# TSC-schema.net
KiCad netlist of a schematic drawn in EAGLE
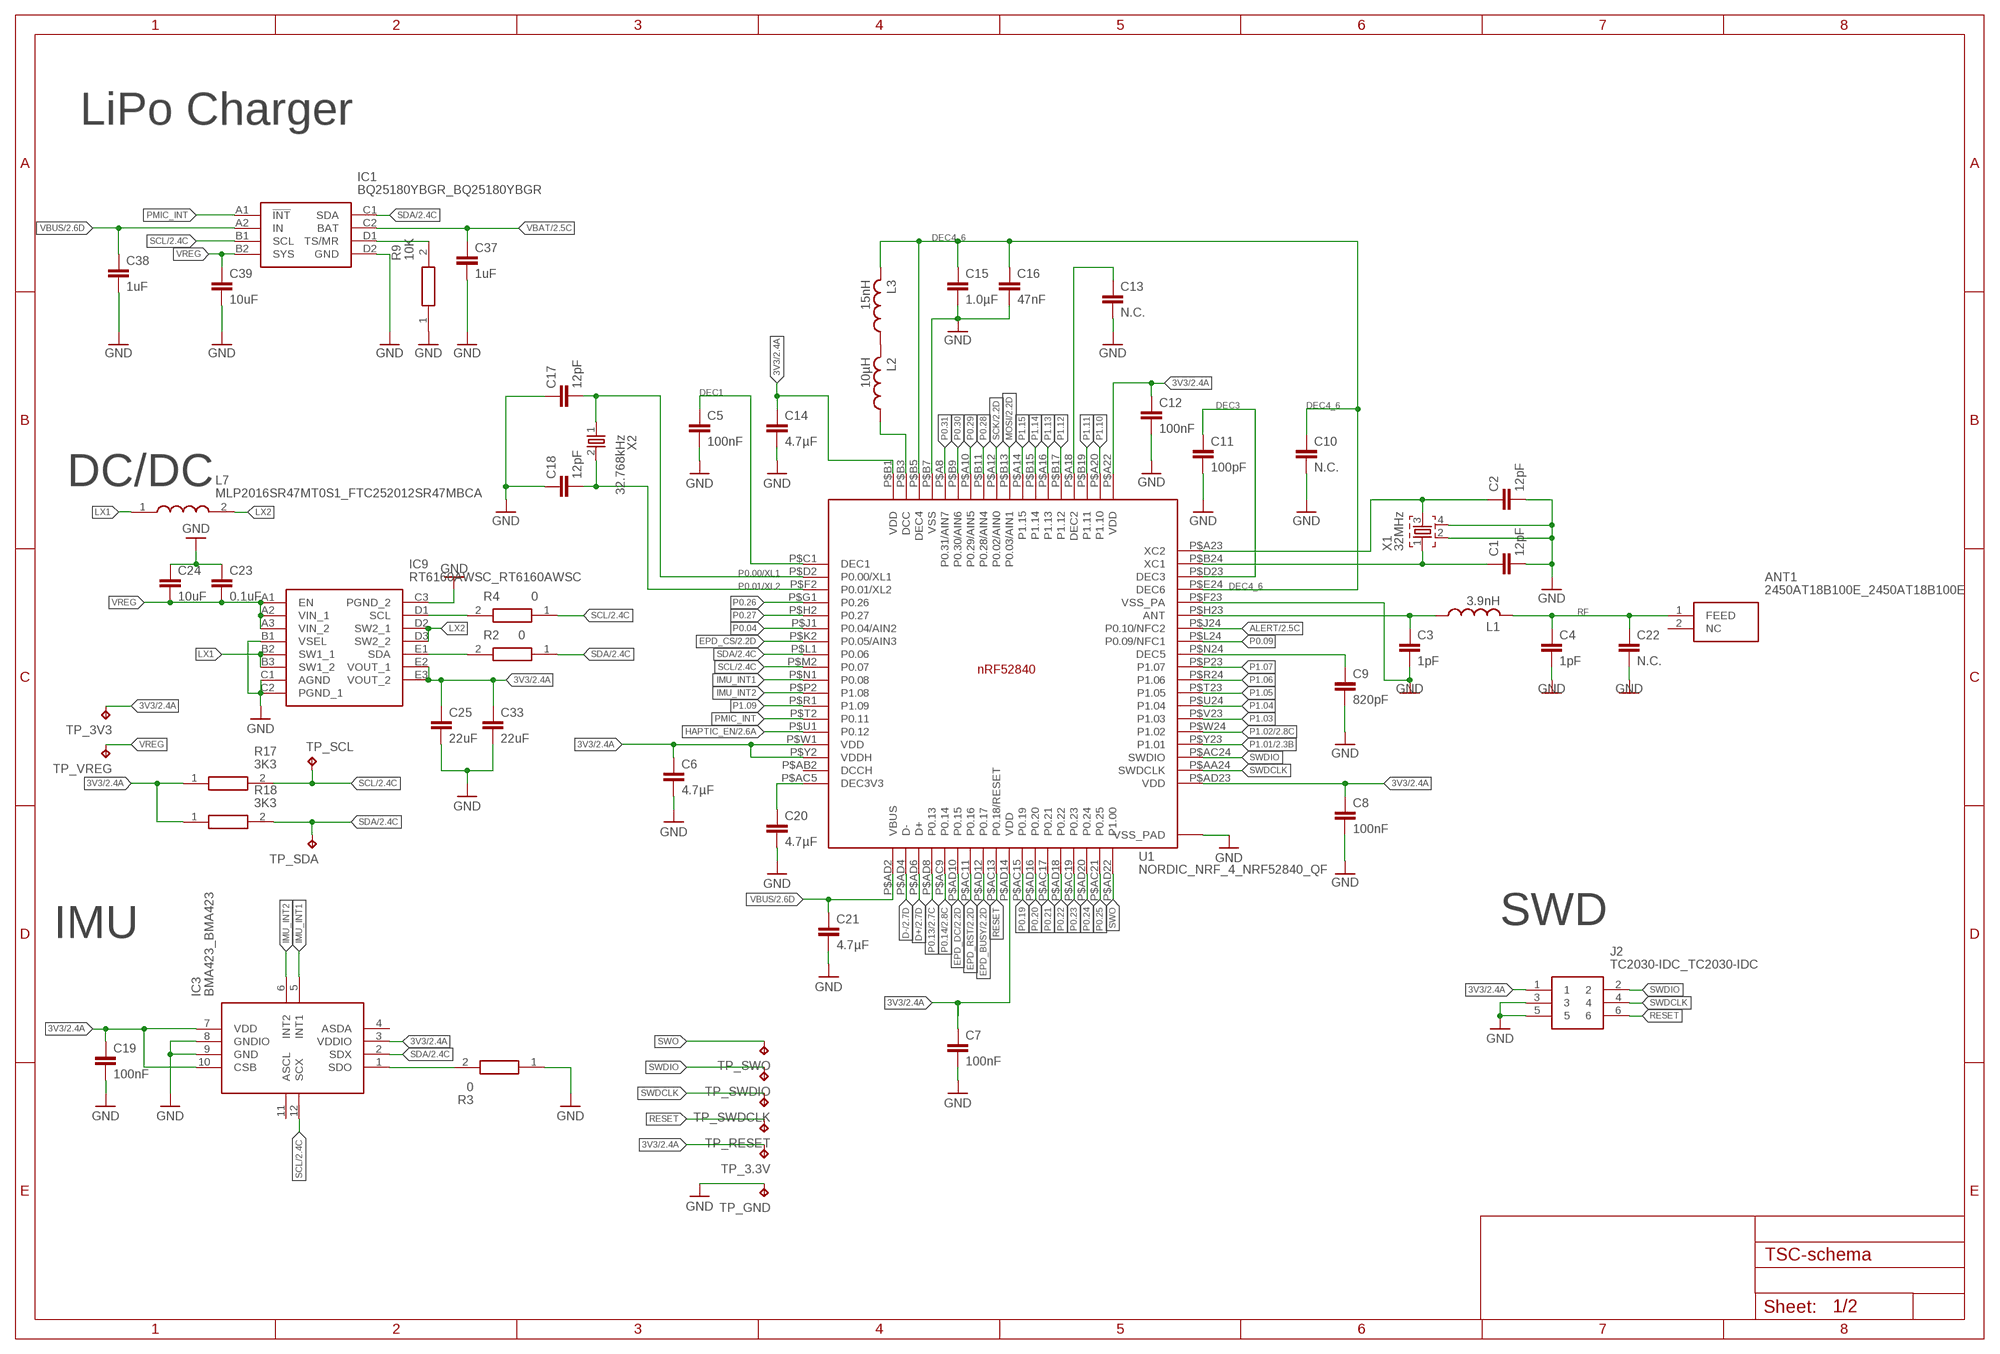
[diagram p0: schematic, sheet 1]
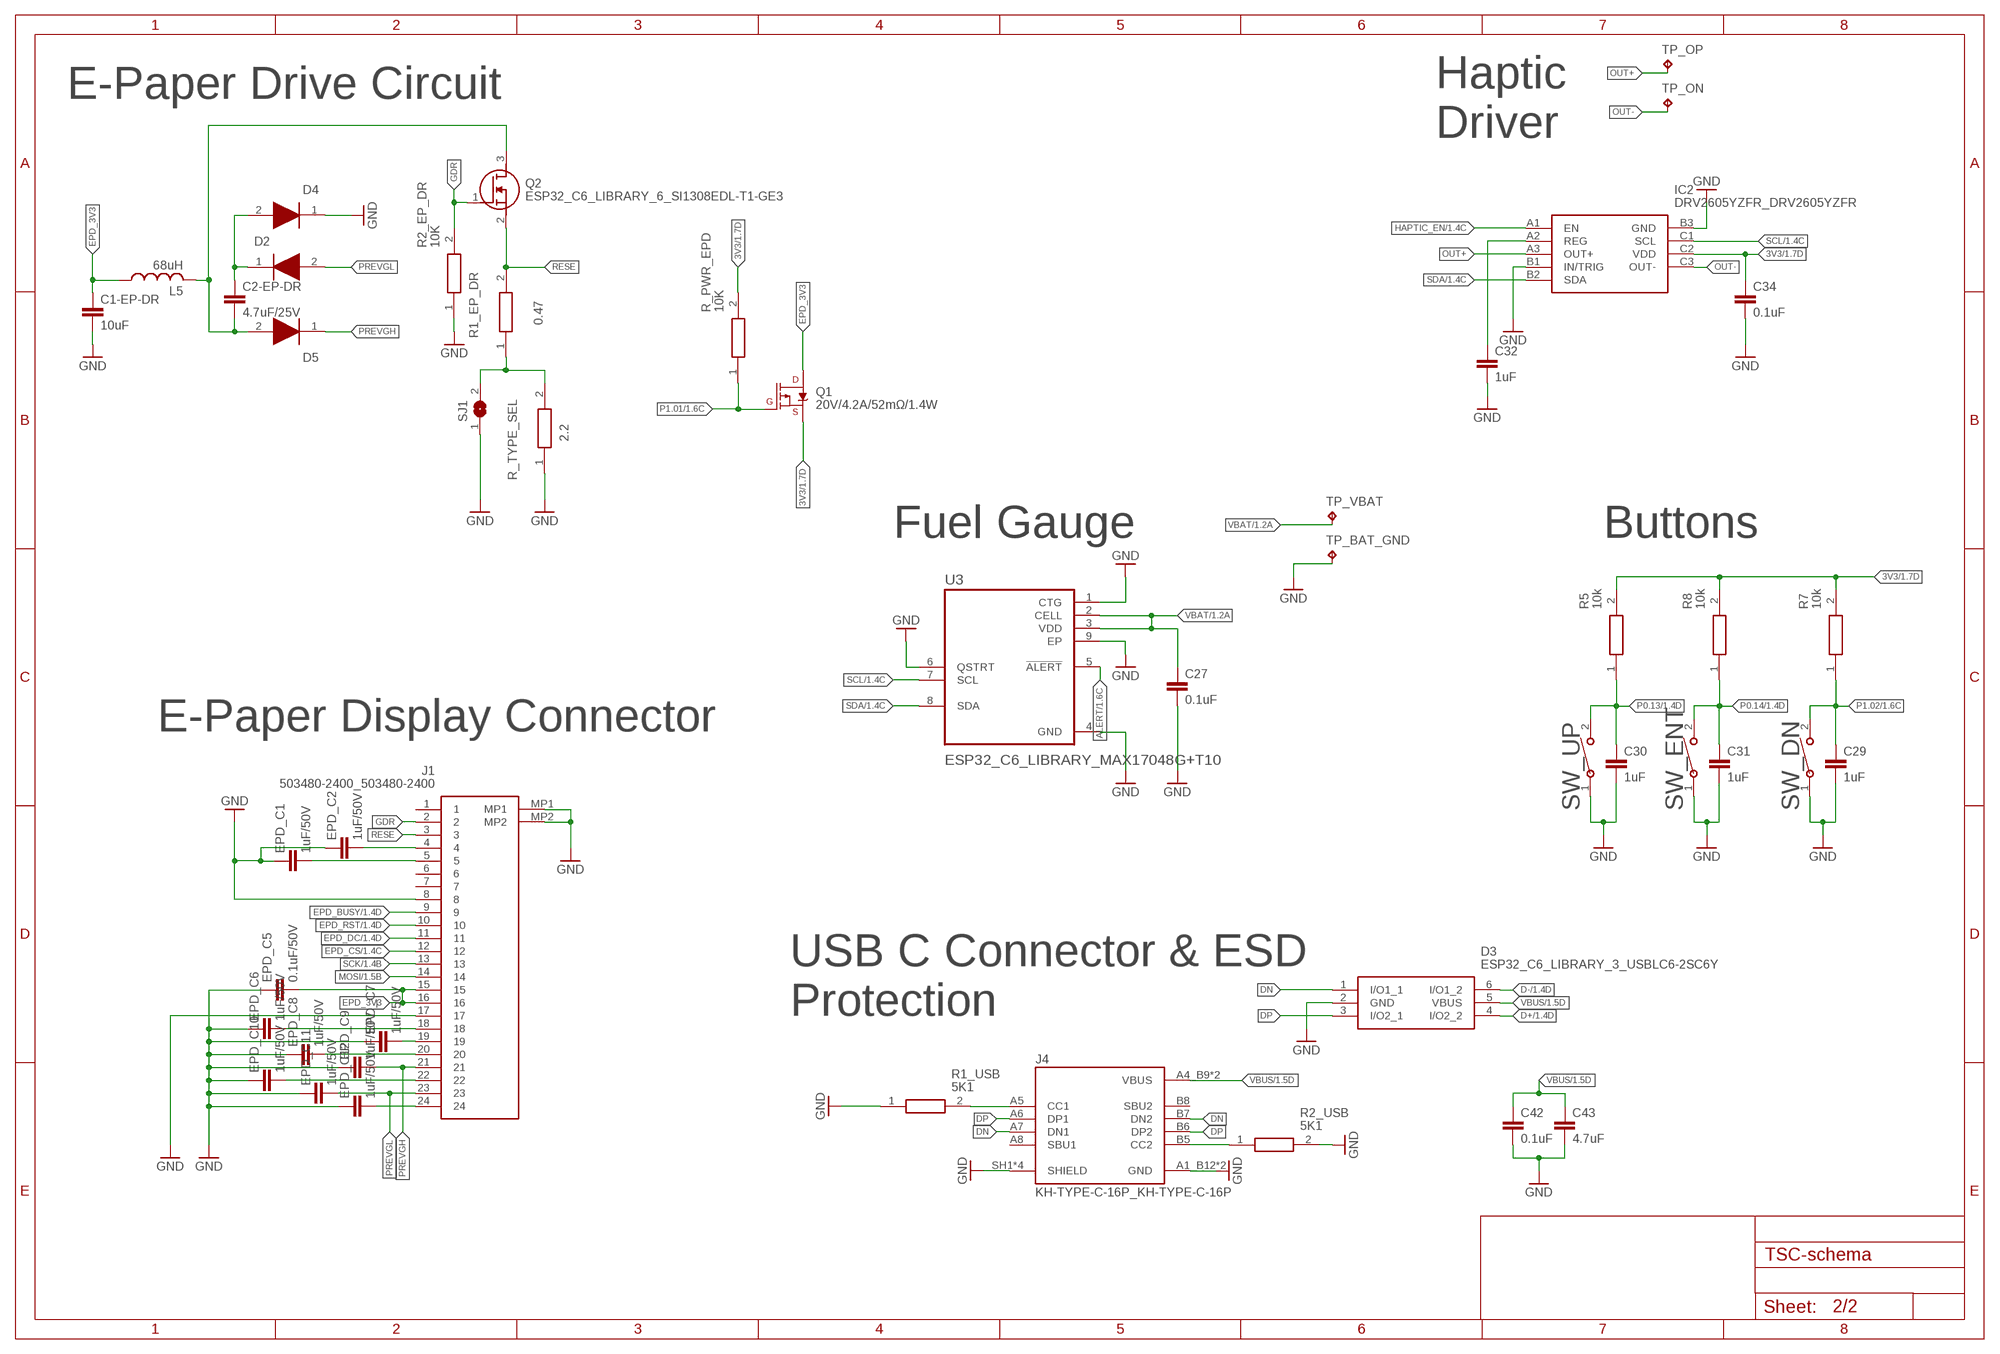
[diagram p1: schematic, sheet 2]

(export (version "E")
  (design (tool "Eeschema 10.0.6"))
  (components
    (comp (ref "ANT1")
      (value "2450AT18B100E_2450AT18B100E")
      (footprint "eagle-import:2450AT18B100E_ANTC3216X140N")
      (fields
        (field (name "ARROW_PART_NUMBER") "2450AT18B100E")
        (field (name "MOUSER_PART_NUMBER") "609-2450AT18B100E")
      )
      (libsource (lib "eagle-import") (part "2450AT18B100E_2450AT18B100E"))
    )
    (comp (ref "C1")
      (value "12pF")
      (footprint "eagle-import:NORDIC_NRF_3_RESC0201_L")
      (libsource (lib "eagle-import") (part "NORDIC_NRF_3_CAPACITOR_0201_L"))
    )
    (comp (ref "C2")
      (value "12pF")
      (footprint "eagle-import:NORDIC_NRF_3_RESC0201_L")
      (libsource (lib "eagle-import") (part "NORDIC_NRF_3_CAPACITOR_0201_L"))
    )
    (comp (ref "C3")
      (value "1pF")
      (footprint "eagle-import:NORDIC_NRF_3_RESC0201_L")
      (libsource (lib "eagle-import") (part "NORDIC_NRF_3_CAPACITOR_0201_L"))
    )
    (comp (ref "C4")
      (value "1pF")
      (footprint "eagle-import:NORDIC_NRF_3_RESC0201_L")
      (libsource (lib "eagle-import") (part "NORDIC_NRF_3_CAPACITOR_0201_L"))
    )
    (comp (ref "C5")
      (value "100nF")
      (footprint "eagle-import:NORDIC_NRF_3_RESC0201_L")
      (libsource (lib "eagle-import") (part "NORDIC_NRF_3_CAPACITOR_0201_L"))
    )
    (comp (ref "C6")
      (value "4.7µF")
      (footprint "eagle-import:NORDIC_NRF_3_RESC0201_L")
      (libsource (lib "eagle-import") (part "NORDIC_NRF_3_CAPACITOR_0201_L"))
    )
    (comp (ref "C7")
      (value "100nF")
      (footprint "eagle-import:NORDIC_NRF_3_RESC0201_L")
      (libsource (lib "eagle-import") (part "NORDIC_NRF_3_CAPACITOR_0201_L"))
    )
    (comp (ref "C8")
      (value "100nF")
      (footprint "eagle-import:NORDIC_NRF_3_RESC0201_L")
      (libsource (lib "eagle-import") (part "NORDIC_NRF_3_CAPACITOR_0201_L"))
    )
    (comp (ref "C9")
      (value "820pF")
      (footprint "eagle-import:NORDIC_NRF_3_RESC0201_L")
      (libsource (lib "eagle-import") (part "NORDIC_NRF_3_CAPACITOR_0201_L"))
    )
    (comp (ref "C10")
      (value "N.C.")
      (footprint "eagle-import:NORDIC_NRF_3_RESC0201_L")
      (libsource (lib "eagle-import") (part "NORDIC_NRF_3_CAPACITOR_0201_L"))
    )
    (comp (ref "C11")
      (value "100pF")
      (footprint "eagle-import:NORDIC_NRF_3_RESC0201_L")
      (libsource (lib "eagle-import") (part "NORDIC_NRF_3_CAPACITOR_0201_L"))
    )
    (comp (ref "C12")
      (value "100nF")
      (footprint "eagle-import:NORDIC_NRF_3_RESC0201_L")
      (libsource (lib "eagle-import") (part "NORDIC_NRF_3_CAPACITOR_0201_L"))
    )
    (comp (ref "C13")
      (value "N.C.")
      (footprint "eagle-import:NORDIC_NRF_3_RESC0201_L")
      (libsource (lib "eagle-import") (part "NORDIC_NRF_3_CAPACITOR_0201_L"))
    )
    (comp (ref "C14")
      (value "4.7µF")
      (footprint "eagle-import:NORDIC_NRF_3_RESC0201_L")
      (libsource (lib "eagle-import") (part "NORDIC_NRF_3_CAPACITOR_0201_L"))
    )
    (comp (ref "C15")
      (value "1.0µF")
      (footprint "eagle-import:NORDIC_NRF_3_RESC0201_L")
      (libsource (lib "eagle-import") (part "NORDIC_NRF_3_CAPACITOR_0201_L"))
    )
    (comp (ref "C16")
      (value "47nF")
      (footprint "eagle-import:NORDIC_NRF_3_RESC0201_L")
      (libsource (lib "eagle-import") (part "NORDIC_NRF_3_CAPACITOR_0201_L"))
    )
    (comp (ref "C17")
      (value "12pF")
      (footprint "eagle-import:NORDIC_NRF_3_RESC0201_L")
      (libsource (lib "eagle-import") (part "NORDIC_NRF_3_CAPACITOR_0201_L"))
    )
    (comp (ref "C18")
      (value "12pF")
      (footprint "eagle-import:NORDIC_NRF_3_RESC0201_L")
      (libsource (lib "eagle-import") (part "NORDIC_NRF_3_CAPACITOR_0201_L"))
    )
    (comp (ref "C19")
      (value "100nF")
      (footprint "eagle-import:NORDIC_NRF_3_RESC0201_L")
      (libsource (lib "eagle-import") (part "NORDIC_NRF_3_CAPACITOR_0201_L"))
    )
    (comp (ref "C20")
      (value "4.7µF")
      (footprint "eagle-import:NORDIC_NRF_3_RESC0201_L")
      (libsource (lib "eagle-import") (part "NORDIC_NRF_3_CAPACITOR_0201_L"))
    )
    (comp (ref "C21")
      (value "4.7µF")
      (footprint "eagle-import:NORDIC_NRF_3_RESC0201_L")
      (libsource (lib "eagle-import") (part "NORDIC_NRF_3_CAPACITOR_0201_L"))
    )
    (comp (ref "C22")
      (value "N.C.")
      (footprint "eagle-import:NORDIC_NRF_3_RESC0201_L")
      (libsource (lib "eagle-import") (part "NORDIC_NRF_3_CAPACITOR_0201_L"))
    )
    (comp (ref "C23")
      (value "0.1uF")
      (footprint "eagle-import:NORDIC_NRF_3_RESC0201_L")
      (libsource (lib "eagle-import") (part "NORDIC_NRF_3_CAPACITOR_0201_L"))
    )
    (comp (ref "C24")
      (value "10uF")
      (footprint "eagle-import:NORDIC_NRF_3_RESC0201_L")
      (libsource (lib "eagle-import") (part "NORDIC_NRF_3_CAPACITOR_0201_L"))
    )
    (comp (ref "C25")
      (value "22uF")
      (footprint "eagle-import:NORDIC_NRF_3_RESC0201_L")
      (libsource (lib "eagle-import") (part "NORDIC_NRF_3_CAPACITOR_0201_L"))
    )
    (comp (ref "C33")
      (value "22uF")
      (footprint "eagle-import:NORDIC_NRF_3_RESC0201_L")
      (libsource (lib "eagle-import") (part "NORDIC_NRF_3_CAPACITOR_0201_L"))
    )
    (comp (ref "C37")
      (value "1uF")
      (footprint "eagle-import:NORDIC_NRF_3_RESC0402_L")
      (libsource (lib "eagle-import") (part "NORDIC_NRF_3_CAPACITOR_0402_L"))
    )
    (comp (ref "C38")
      (value "1uF")
      (footprint "eagle-import:NORDIC_NRF_3_RESC0402_L")
      (libsource (lib "eagle-import") (part "NORDIC_NRF_3_CAPACITOR_0402_L"))
    )
    (comp (ref "C39")
      (value "10uF")
      (footprint "eagle-import:NORDIC_NRF_3_RESC0201_L")
      (libsource (lib "eagle-import") (part "NORDIC_NRF_3_CAPACITOR_0201_L"))
    )
    (comp (ref "IC1")
      (value "BQ25180YBGR_BQ25180YBGR")
      (footprint "eagle-import:BQ25180YBGR_BGA8C40P2X4_100X155X50")
      (fields
        (field (name "ARROW_PART_NUMBER") "BQ25180YBGR")
        (field (name "MOUSER_PART_NUMBER") "595-BQ25180YBGR")
      )
      (libsource (lib "eagle-import") (part "BQ25180YBGR_BQ25180YBGR"))
    )
    (comp (ref "IC3")
      (value "BMA423_BMA423")
      (footprint "eagle-import:BMA423_BMA423")
      (fields (field (name "ARROW_PART_NUMBER") "BMA423") (field (name "MOUSER_PART_NUMBER") "262-BMA423"))
      (libsource (lib "eagle-import") (part "BMA423_BMA423"))
    )
    (comp (ref "IC9")
      (value "RT6160AWSC_RT6160AWSC")
      (footprint "eagle-import:RT6160AWSC_BGA15C40P3X5_140X230X60")
      (fields
        (field (name "MANUFACTURER_PART_NUMBER") "RT6160AWSC")
        (field (name "MOUSER_PART_NUMBER") "835-RT6160AWSC")
      )
      (libsource (lib "eagle-import") (part "RT6160AWSC_RT6160AWSC"))
    )
    (comp (ref "J2")
      (value "TC2030-IDC_TC2030-IDC")
      (footprint "eagle-import:TC2030-IDC_TC2030IDC")
      (fields (field (name "MANUFACTURER_PART_NUMBER") "TC2030-IDC"))
      (libsource (lib "eagle-import") (part "TC2030-IDC_TC2030-IDC"))
    )
    (comp (ref "L1")
      (value "3.9nH")
      (footprint "eagle-import:NORDIC_NRF_2_RESC0402_L")
      (libsource (lib "eagle-import") (part "NORDIC_NRF_2_INDUCTOR_0402_L"))
    )
    (comp (ref "L2")
      (value "10µH")
      (footprint "eagle-import:NORDIC_NRF_2_RESC0402_L")
      (libsource (lib "eagle-import") (part "NORDIC_NRF_2_INDUCTOR_0402_L"))
    )
    (comp (ref "L3")
      (value "15nH")
      (footprint "eagle-import:NORDIC_NRF_2_RESC0402_L")
      (libsource (lib "eagle-import") (part "NORDIC_NRF_2_INDUCTOR_0402_L"))
    )
    (comp (ref "L7")
      (value "MLP2016SR47MT0S1_FTC252012SR47MBCA")
      (footprint "eagle-import:MLP2016SR47MT0S1_INDC2016X100N")
      (fields (field (name "MANUFACTURER_PART_NUMBER") "FTC252012SR47MBCA"))
      (libsource (lib "eagle-import") (part "MLP2016SR47MT0S1_FTC252012SR47MBCA"))
    )
    (comp (ref "R2")
      (value "0")
      (footprint "eagle-import:CPF0201D7K68C1_0201")
      (libsource (lib "eagle-import") (part "CPF0201D7K68C1_CPF0201D7K68C1"))
    )
    (comp (ref "R3")
      (value "0")
      (footprint "eagle-import:CPF0201D7K68C1_0201")
      (libsource (lib "eagle-import") (part "CPF0201D7K68C1_CPF0201D7K68C1"))
    )
    (comp (ref "R4")
      (value "0")
      (footprint "eagle-import:CPF0201D7K68C1_0201")
      (libsource (lib "eagle-import") (part "CPF0201D7K68C1_CPF0201D7K68C1"))
    )
    (comp (ref "R9")
      (value "10K")
      (footprint "eagle-import:CPF0201D7K68C1_0201")
      (libsource (lib "eagle-import") (part "CPF0201D7K68C1_CPF0201D7K68C1"))
    )
    (comp (ref "R17")
      (value "3K3")
      (footprint "eagle-import:CPF0201D7K68C1_0201")
      (libsource (lib "eagle-import") (part "CPF0201D7K68C1_CPF0201D7K68C1"))
    )
    (comp (ref "R18")
      (value "3K3")
      (footprint "eagle-import:CPF0201D7K68C1_0201")
      (libsource (lib "eagle-import") (part "CPF0201D7K68C1_CPF0201D7K68C1"))
    )
    (comp (ref "TP_3.3V")
      (value "HECTOR_WATCH_1_TPTP20R")
      (footprint "eagle-import:HECTOR_WATCH_1_TP20R")
      (libsource (lib "eagle-import") (part "HECTOR_WATCH_1_TPTP20R"))
    )
    (comp (ref "TP_3V3")
      (value "HECTOR_WATCH_1_TPTP20R")
      (footprint "eagle-import:HECTOR_WATCH_1_TP20R")
      (libsource (lib "eagle-import") (part "HECTOR_WATCH_1_TPTP20R"))
    )
    (comp (ref "TP_GND")
      (value "HECTOR_WATCH_1_TPTP20R")
      (footprint "eagle-import:HECTOR_WATCH_1_TP20R")
      (libsource (lib "eagle-import") (part "HECTOR_WATCH_1_TPTP20R"))
    )
    (comp (ref "TP_RESET")
      (value "HECTOR_WATCH_1_TPTP20R")
      (footprint "eagle-import:HECTOR_WATCH_1_TP20R")
      (libsource (lib "eagle-import") (part "HECTOR_WATCH_1_TPTP20R"))
    )
    (comp (ref "TP_SCL")
      (value "HECTOR_WATCH_1_TPTP20R")
      (footprint "eagle-import:HECTOR_WATCH_1_TP20R")
      (libsource (lib "eagle-import") (part "HECTOR_WATCH_1_TPTP20R"))
    )
    (comp (ref "TP_SDA")
      (value "HECTOR_WATCH_1_TPTP20R")
      (footprint "eagle-import:HECTOR_WATCH_1_TP20R")
      (libsource (lib "eagle-import") (part "HECTOR_WATCH_1_TPTP20R"))
    )
    (comp (ref "TP_SWDCLK")
      (value "HECTOR_WATCH_1_TPTP20R")
      (footprint "eagle-import:HECTOR_WATCH_1_TP20R")
      (libsource (lib "eagle-import") (part "HECTOR_WATCH_1_TPTP20R"))
    )
    (comp (ref "TP_SWDIO")
      (value "HECTOR_WATCH_1_TPTP20R")
      (footprint "eagle-import:HECTOR_WATCH_1_TP20R")
      (libsource (lib "eagle-import") (part "HECTOR_WATCH_1_TPTP20R"))
    )
    (comp (ref "TP_SWO")
      (value "HECTOR_WATCH_1_TPTP20R")
      (footprint "eagle-import:HECTOR_WATCH_1_TP20R")
      (libsource (lib "eagle-import") (part "HECTOR_WATCH_1_TPTP20R"))
    )
    (comp (ref "TP_VREG")
      (value "HECTOR_WATCH_1_TPTP20R")
      (footprint "eagle-import:HECTOR_WATCH_1_TP20R")
      (libsource (lib "eagle-import") (part "HECTOR_WATCH_1_TPTP20R"))
    )
    (comp (ref "U1")
      (value "NORDIC_NRF_4_NRF52840_QF")
      (footprint "eagle-import:NORDIC_NRF_4_AQFN50P700X700X85_HS-74N")
      (libsource (lib "eagle-import") (part "NORDIC_NRF_4_NRF52840_QF"))
    )
    (comp (ref "X1")
      (value "32MHz")
      (footprint "eagle-import:NORDIC_NRF_BT-XTAL_2016_N")
      (libsource (lib "eagle-import") (part "NORDIC_NRF_XTAL_32MHZ"))
    )
    (comp (ref "X2")
      (value "32.768kHz")
      (footprint "eagle-import:NORDIC_NRF_1_XTAL_3215_N")
      (libsource (lib "eagle-import") (part "NORDIC_NRF_1_XTAL_32KHZ"))
    )
    (comp (ref "C1-EP-DR")
      (value "10uF")
      (footprint "eagle-import:NORDIC_NRF_3_RESC0402_L")
      (libsource (lib "eagle-import") (part "NORDIC_NRF_3_CAPACITOR_0402_L"))
    )
    (comp (ref "C2-EP-DR")
      (value "4.7uF/25V")
      (footprint "eagle-import:NORDIC_NRF_3_RESC0201_L")
      (libsource (lib "eagle-import") (part "NORDIC_NRF_3_CAPACITOR_0201_L"))
    )
    (comp (ref "C27")
      (value "0.1uF")
      (footprint "eagle-import:NORDIC_NRF_3_RESC0201_L")
      (libsource (lib "eagle-import") (part "NORDIC_NRF_3_CAPACITOR_0201_L"))
    )
    (comp (ref "C29")
      (value "1uF")
      (footprint "eagle-import:NORDIC_NRF_3_RESC0402_L")
      (libsource (lib "eagle-import") (part "NORDIC_NRF_3_CAPACITOR_0402_L"))
    )
    (comp (ref "C30")
      (value "1uF")
      (footprint "eagle-import:NORDIC_NRF_3_RESC0402_L")
      (libsource (lib "eagle-import") (part "NORDIC_NRF_3_CAPACITOR_0402_L"))
    )
    (comp (ref "C31")
      (value "1uF")
      (footprint "eagle-import:NORDIC_NRF_3_RESC0402_L")
      (libsource (lib "eagle-import") (part "NORDIC_NRF_3_CAPACITOR_0402_L"))
    )
    (comp (ref "C32")
      (value "1uF")
      (footprint "eagle-import:NORDIC_NRF_3_RESC0402_L")
      (libsource (lib "eagle-import") (part "NORDIC_NRF_3_CAPACITOR_0402_L"))
    )
    (comp (ref "C34")
      (value "0.1uF")
      (footprint "eagle-import:NORDIC_NRF_3_RESC0201_L")
      (libsource (lib "eagle-import") (part "NORDIC_NRF_3_CAPACITOR_0201_L"))
    )
    (comp (ref "C42")
      (value "0.1uF")
      (footprint "eagle-import:NORDIC_NRF_3_RESC0201_L")
      (libsource (lib "eagle-import") (part "NORDIC_NRF_3_CAPACITOR_0201_L"))
    )
    (comp (ref "C43")
      (value "4.7uF")
      (footprint "eagle-import:NORDIC_NRF_3_RESC0201_L")
      (libsource (lib "eagle-import") (part "NORDIC_NRF_3_CAPACITOR_0201_L"))
    )
    (comp (ref "D2")
      (value "ESP32_C6_LIBRARY_5_MBR0530")
      (footprint "eagle-import:ESP32_C6_LIBRARY_5_SOD3716X135N")
      (fields (field (name "MF") "ON Semiconductor") (field (name "MP") "MBR0530"))
      (libsource (lib "eagle-import") (part "ESP32_C6_LIBRARY_5_MBR0530"))
    )
    (comp (ref "D3")
      (value "ESP32_C6_LIBRARY_3_USBLC6-2SC6Y")
      (footprint "eagle-import:ESP32_C6_LIBRARY_3_SOT95P280X145-6N")
      (fields (field (name "MF") "STMicroelectronics") (field (name "MP") "USBLC6-2SC6Y"))
      (libsource (lib "eagle-import") (part "ESP32_C6_LIBRARY_3_USBLC6-2SC6Y"))
    )
    (comp (ref "D4")
      (value "ESP32_C6_LIBRARY_5_MBR0530")
      (footprint "eagle-import:ESP32_C6_LIBRARY_5_SOD3716X135N")
      (fields (field (name "MF") "ON Semiconductor") (field (name "MP") "MBR0530"))
      (libsource (lib "eagle-import") (part "ESP32_C6_LIBRARY_5_MBR0530"))
    )
    (comp (ref "D5")
      (value "ESP32_C6_LIBRARY_5_MBR0530")
      (footprint "eagle-import:ESP32_C6_LIBRARY_5_SOD3716X135N")
      (fields (field (name "MF") "ON Semiconductor") (field (name "MP") "MBR0530"))
      (libsource (lib "eagle-import") (part "ESP32_C6_LIBRARY_5_MBR0530"))
    )
    (comp (ref "EPD_C1")
      (value "1uF/50V")
      (footprint "eagle-import:NORDIC_NRF_3_RESC0201_L")
      (libsource (lib "eagle-import") (part "NORDIC_NRF_3_CAPACITOR_0201_L"))
    )
    (comp (ref "EPD_C2")
      (value "1uF/50V")
      (footprint "eagle-import:NORDIC_NRF_3_RESC0201_L")
      (libsource (lib "eagle-import") (part "NORDIC_NRF_3_CAPACITOR_0201_L"))
    )
    (comp (ref "EPD_C5")
      (value "0.1uF/50V")
      (footprint "eagle-import:NORDIC_NRF_3_RESC0201_L")
      (libsource (lib "eagle-import") (part "NORDIC_NRF_3_CAPACITOR_0201_L"))
    )
    (comp (ref "EPD_C6")
      (value "1uF/50V")
      (footprint "eagle-import:NORDIC_NRF_3_RESC0201_L")
      (libsource (lib "eagle-import") (part "NORDIC_NRF_3_CAPACITOR_0201_L"))
    )
    (comp (ref "EPD_C7")
      (value "1uF/50V")
      (footprint "eagle-import:NORDIC_NRF_3_RESC0201_L")
      (libsource (lib "eagle-import") (part "NORDIC_NRF_3_CAPACITOR_0201_L"))
    )
    (comp (ref "EPD_C8")
      (value "1uF/50V")
      (footprint "eagle-import:NORDIC_NRF_3_RESC0201_L")
      (libsource (lib "eagle-import") (part "NORDIC_NRF_3_CAPACITOR_0201_L"))
    )
    (comp (ref "EPD_C9")
      (value "1uF/50V")
      (footprint "eagle-import:NORDIC_NRF_3_RESC0201_L")
      (libsource (lib "eagle-import") (part "NORDIC_NRF_3_CAPACITOR_0201_L"))
    )
    (comp (ref "EPD_C10")
      (value "1uF/50V")
      (footprint "eagle-import:NORDIC_NRF_3_RESC0201_L")
      (libsource (lib "eagle-import") (part "NORDIC_NRF_3_CAPACITOR_0201_L"))
    )
    (comp (ref "EPD_C11")
      (value "1uF/50V")
      (footprint "eagle-import:NORDIC_NRF_3_RESC0201_L")
      (libsource (lib "eagle-import") (part "NORDIC_NRF_3_CAPACITOR_0201_L"))
    )
    (comp (ref "EPD_C12")
      (value "1uF/50V")
      (footprint "eagle-import:NORDIC_NRF_3_RESC0201_L")
      (libsource (lib "eagle-import") (part "NORDIC_NRF_3_CAPACITOR_0201_L"))
    )
    (comp (ref "IC2")
      (value "DRV2605YZFR_DRV2605YZFR")
      (footprint "eagle-import:DRV2605YZFR_BGA9C50P3X3_144X144X62")
      (fields (field (name "ARROW_PART_NUMBER") "DRV2605YZFR"))
      (libsource (lib "eagle-import") (part "DRV2605YZFR_DRV2605YZFR"))
    )
    (comp (ref "J1")
      (value "503480-2400_503480-2400")
      (footprint "eagle-import:503480-2400_5034802400")
      (fields
        (field (name "MANUFACTURER_PART_NUMBER") "503480-2400")
        (field (name "MOUSER_PART_NUMBER") "538-503480-2400")
      )
      (libsource (lib "eagle-import") (part "503480-2400_503480-2400"))
    )
    (comp (ref "J4")
      (value "KH-TYPE-C-16P_KH-TYPE-C-16P")
      (footprint "eagle-import:KH-TYPE-C-16P_KINGHELM_KH-TYPE-C-16P")
      (fields (field (name "MF") "kinghelm") (field (name "MP") "KH-TYPE-C-16P"))
      (libsource (lib "eagle-import") (part "KH-TYPE-C-16P_KH-TYPE-C-16P"))
    )
    (comp (ref "L5")
      (value "68uH")
      (footprint "eagle-import:NORDIC_NRF_2_RESC0402_L")
      (libsource (lib "eagle-import") (part "NORDIC_NRF_2_INDUCTOR_0402_L"))
    )
    (comp (ref "Q1")
      (value "20V/4.2A/52mΩ/1.4W")
      (footprint "eagle-import:ESP32_C6_LIBRARY_4_ESP32_C6_LIBRARY_4_ESP32_C6_LIBRARY_4_ESP32_C6_LIBRARY_4_ESP32_WROVER_SPARKFUN-DISCRETESEMI_SOT23-3")
      (libsource (lib "eagle-import") (part "ESP32_C6_LIBRARY_4_ESP32_WROVER_SPARKFUN-DISCRETESEMI_MOSFET_PCH-DMG2305UX-7"))
    )
    (comp (ref "Q2")
      (value "ESP32_C6_LIBRARY_6_SI1308EDL-T1-GE3")
      (footprint "eagle-import:ESP32_C6_LIBRARY_6_SOT65P210X110-3N")
      (fields (field (name "MF") "Vishay Siliconix") (field (name "MP") "SI1308EDL-T1-GE3"))
      (libsource (lib "eagle-import") (part "ESP32_C6_LIBRARY_6_SI1308EDL-T1-GE3"))
    )
    (comp (ref "R1_EP_DR")
      (value "0.47")
      (footprint "eagle-import:CPF0201D7K68C1_0201")
      (libsource (lib "eagle-import") (part "CPF0201D7K68C1_CPF0201D7K68C1"))
    )
    (comp (ref "R1_USB")
      (value "5K1")
      (footprint "eagle-import:CPF0201D7K68C1_0201")
      (libsource (lib "eagle-import") (part "CPF0201D7K68C1_CPF0201D7K68C1"))
    )
    (comp (ref "R2_EP_DR")
      (value "10K")
      (footprint "eagle-import:CPF0201D7K68C1_0201")
      (libsource (lib "eagle-import") (part "CPF0201D7K68C1_CPF0201D7K68C1"))
    )
    (comp (ref "R2_USB")
      (value "5K1")
      (footprint "eagle-import:CPF0201D7K68C1_0201")
      (libsource (lib "eagle-import") (part "CPF0201D7K68C1_CPF0201D7K68C1"))
    )
    (comp (ref "R5")
      (value "10k")
      (footprint "eagle-import:CPF0201D7K68C1_0201")
      (libsource (lib "eagle-import") (part "CPF0201D7K68C1_CPF0201D7K68C1"))
    )
    (comp (ref "R7")
      (value "10k")
      (footprint "eagle-import:CPF0201D7K68C1_0201")
      (libsource (lib "eagle-import") (part "CPF0201D7K68C1_CPF0201D7K68C1"))
    )
    (comp (ref "R8")
      (value "10k")
      (footprint "eagle-import:CPF0201D7K68C1_0201")
      (libsource (lib "eagle-import") (part "CPF0201D7K68C1_CPF0201D7K68C1"))
    )
    (comp (ref "R_PWR_EPD")
      (value "10K")
      (footprint "eagle-import:CPF0201D7K68C1_0201")
      (libsource (lib "eagle-import") (part "CPF0201D7K68C1_CPF0201D7K68C1"))
    )
    (comp (ref "R_TYPE_SEL")
      (value "2.2")
      (footprint "eagle-import:CPF0201D7K68C1_0201")
      (libsource (lib "eagle-import") (part "CPF0201D7K68C1_CPF0201D7K68C1"))
    )
    (comp (ref "SJ1")
      (value "ESP32_C6_LIBRARY_7_JUMPER_SJ")
      (footprint "eagle-import:ESP32_C6_LIBRARY_7_JUMPER_SJ")
      (libsource (lib "eagle-import") (part "ESP32_C6_LIBRARY_7_JUMPER_SJ"))
    )
    (comp (ref "SW_DN")
      (value "2025-10-22_07-23-44_LIBRARY_EVP-AKE31ASW_EVP-AKE31A_PAN")
      (footprint "eagle-import:2025-10-22_07-23-44_LIBRARY_SW_EVP-AKE31A_PAN")
      (fields
        (field (name "MANUFACTURER_PART_NUMBER") "EVP-AKE31A")
        (field (name "COPYRIGHT") "Copyright (C) 2025 Ultra Librarian. All rights reserved.")
      )
      (libsource (lib "eagle-import") (part "2025-10-22_07-23-44_LIBRARY_EVP-AKE31ASW_EVP-AKE31A_PAN"))
    )
    (comp (ref "SW_ENT")
      (value "2025-10-22_07-23-44_LIBRARY_EVP-AKE31ASW_EVP-AKE31A_PAN")
      (footprint "eagle-import:2025-10-22_07-23-44_LIBRARY_SW_EVP-AKE31A_PAN")
      (fields
        (field (name "MANUFACTURER_PART_NUMBER") "EVP-AKE31A")
        (field (name "COPYRIGHT") "Copyright (C) 2025 Ultra Librarian. All rights reserved.")
      )
      (libsource (lib "eagle-import") (part "2025-10-22_07-23-44_LIBRARY_EVP-AKE31ASW_EVP-AKE31A_PAN"))
    )
    (comp (ref "SW_UP")
      (value "2025-10-22_07-23-44_LIBRARY_EVP-AKE31ASW_EVP-AKE31A_PAN")
      (footprint "eagle-import:2025-10-22_07-23-44_LIBRARY_SW_EVP-AKE31A_PAN")
      (fields
        (field (name "MANUFACTURER_PART_NUMBER") "EVP-AKE31A")
        (field (name "COPYRIGHT") "Copyright (C) 2025 Ultra Librarian. All rights reserved.")
      )
      (libsource (lib "eagle-import") (part "2025-10-22_07-23-44_LIBRARY_EVP-AKE31ASW_EVP-AKE31A_PAN"))
    )
    (comp (ref "TP_BAT_GND")
      (value "HECTOR_WATCH_1_TPTP20R")
      (footprint "eagle-import:HECTOR_WATCH_1_TP20R")
      (libsource (lib "eagle-import") (part "HECTOR_WATCH_1_TPTP20R"))
    )
    (comp (ref "TP_ON")
      (value "HECTOR_WATCH_1_TPTP20R")
      (footprint "eagle-import:HECTOR_WATCH_1_TP20R")
      (libsource (lib "eagle-import") (part "HECTOR_WATCH_1_TPTP20R"))
    )
    (comp (ref "TP_OP")
      (value "HECTOR_WATCH_1_TPTP20R")
      (footprint "eagle-import:HECTOR_WATCH_1_TP20R")
      (libsource (lib "eagle-import") (part "HECTOR_WATCH_1_TPTP20R"))
    )
    (comp (ref "TP_VBAT")
      (value "HECTOR_WATCH_1_TPTP20R")
      (footprint "eagle-import:HECTOR_WATCH_1_TP20R")
      (libsource (lib "eagle-import") (part "HECTOR_WATCH_1_TPTP20R"))
    )
    (comp (ref "U3")
      (value "ESP32_C6_LIBRARY_MAX17048G+T10")
      (footprint "eagle-import:ESP32_C6_LIBRARY_SON50P200X200X80-9N")
      (fields (field (name "MF") "Analog Devices") (field (name "MP") "MAX17048G+T10"))
      (libsource (lib "eagle-import") (part "ESP32_C6_LIBRARY_MAX17048G+T10"))
    )
  )
  (nets
    (net (code "1") (name "3V3{slash}1.7D") (class "Default")
      (node (ref "C34") (pin "1") (pinfunction "1_1") (pintype "passive"))
      (node (ref "IC2") (pin "C2") (pinfunction "VDD_C2") (pintype "bidirectional"))
      (node (ref "Q1") (pin "2") (pinfunction "S_2") (pintype "bidirectional"))
      (node (ref "R5") (pin "2") (pinfunction "2_2") (pintype "bidirectional"))
      (node (ref "R7") (pin "2") (pinfunction "2_2") (pintype "bidirectional"))
      (node (ref "R8") (pin "2") (pinfunction "2_2") (pintype "bidirectional"))
      (node (ref "R_PWR_EPD") (pin "2") (pinfunction "2_2") (pintype "bidirectional"))
    )
    (net (code "2") (name "3V3{slash}2.4A") (class "Default")
      (node (ref "C12") (pin "1") (pinfunction "1_1") (pintype "passive"))
      (node (ref "C14") (pin "1") (pinfunction "1_1") (pintype "passive"))
      (node (ref "C19") (pin "1") (pinfunction "1_1") (pintype "passive"))
      (node (ref "C25") (pin "1") (pinfunction "1_1") (pintype "passive"))
      (node (ref "C33") (pin "1") (pinfunction "1_1") (pintype "passive"))
      (node (ref "C6") (pin "1") (pinfunction "1_1") (pintype "passive"))
      (node (ref "C7") (pin "1") (pinfunction "1_1") (pintype "passive"))
      (node (ref "C8") (pin "1") (pinfunction "1_1") (pintype "passive"))
      (node (ref "IC3") (pin "10") (pinfunction "CSB_10") (pintype "bidirectional"))
      (node (ref "IC3") (pin "3") (pinfunction "VDDIO_3") (pintype "bidirectional"))
      (node (ref "IC3") (pin "7") (pinfunction "VDD_7") (pintype "bidirectional"))
      (node (ref "IC9") (pin "E2") (pinfunction "VOUT_1_E2") (pintype "bidirectional"))
      (node (ref "IC9") (pin "E3") (pinfunction "VOUT_2_E3") (pintype "bidirectional"))
      (node (ref "J2") (pin "1") (pinfunction "1_1") (pintype "bidirectional"))
      (node (ref "R17") (pin "1") (pinfunction "1_1") (pintype "bidirectional"))
      (node (ref "R18") (pin "1") (pinfunction "1_1") (pintype "bidirectional"))
      (node (ref "TP_3.3V") (pin "TP") (pinfunction "TP_TP") (pintype "input"))
      (node (ref "TP_3V3") (pin "TP") (pinfunction "TP_TP") (pintype "input"))
      (node (ref "U1") (pin "P$A22") (pinfunction "VDD_P$A22") (pintype "power_in"))
      (node (ref "U1") (pin "P$AD14") (pinfunction "VDD_P$AD14") (pintype "power_in"))
      (node (ref "U1") (pin "P$AD23") (pinfunction "VDD_P$AD23") (pintype "power_in"))
      (node (ref "U1") (pin "P$B1") (pinfunction "VDD_P$B1") (pintype "power_in"))
      (node (ref "U1") (pin "P$W1") (pinfunction "VDD_P$W1") (pintype "power_in"))
      (node (ref "U1") (pin "P$Y2") (pinfunction "VDDH_P$Y2") (pintype "power_in"))
    )
    (net (code "3") (name "ALERT") (class "Default")
      (node (ref "U1") (pin "P$J24") (pinfunction "P0.10/NFC2_P$J24") (pintype "bidirectional"))
      (node (ref "U3") (pin "5") (pinfunction "~{ALERT}_5") (pintype "output"))
    )
    (net (code "4") (name "D+") (class "Default")
      (node (ref "D3") (pin "4") (pinfunction "I/O2_2_4") (pintype "bidirectional"))
      (node (ref "U1") (pin "P$AD6") (pinfunction "D+_P$AD6") (pintype "bidirectional"))
    )
    (net (code "5") (name "D-") (class "Default")
      (node (ref "D3") (pin "6") (pinfunction "I/O1_2_6") (pintype "bidirectional"))
      (node (ref "U1") (pin "P$AD4") (pinfunction "D-_P$AD4") (pintype "bidirectional"))
    )
    (net (code "6") (name "DEC1") (class "Default")
      (node (ref "C5") (pin "1") (pinfunction "1_1") (pintype "passive"))
      (node (ref "U1") (pin "P$C1") (pinfunction "DEC1_P$C1") (pintype "power_in"))
    )
    (net (code "7") (name "DEC3") (class "Default")
      (node (ref "C11") (pin "1") (pinfunction "1_1") (pintype "passive"))
      (node (ref "U1") (pin "P$D23") (pinfunction "DEC3_P$D23") (pintype "bidirectional"))
    )
    (net (code "8") (name "DEC4_6") (class "Default")
      (node (ref "C10") (pin "1") (pinfunction "1_1") (pintype "passive"))
      (node (ref "C15") (pin "1") (pinfunction "1_1") (pintype "passive"))
      (node (ref "C16") (pin "1") (pinfunction "1_1") (pintype "passive"))
      (node (ref "L3") (pin "2") (pinfunction "2_2") (pintype "passive"))
      (node (ref "U1") (pin "P$B5") (pinfunction "DEC4_P$B5") (pintype "power_in"))
      (node (ref "U1") (pin "P$E24") (pinfunction "DEC6_P$E24") (pintype "bidirectional"))
    )
    (net (code "9") (name "DN") (class "Default")
      (node (ref "D3") (pin "1") (pinfunction "I/O1_1_1") (pintype "bidirectional"))
      (node (ref "J4") (pin "A7") (pinfunction "DN1_A7") (pintype "bidirectional"))
      (node (ref "J4") (pin "B7") (pinfunction "DN2_B7") (pintype "bidirectional"))
    )
    (net (code "10") (name "DP") (class "Default")
      (node (ref "D3") (pin "3") (pinfunction "I/O2_1_3") (pintype "bidirectional"))
      (node (ref "J4") (pin "A6") (pinfunction "DP1_A6") (pintype "bidirectional"))
      (node (ref "J4") (pin "B6") (pinfunction "DP2_B6") (pintype "bidirectional"))
    )
    (net (code "11") (name "EPD_3V3") (class "Default")
      (node (ref "C1-EP-DR") (pin "1") (pinfunction "1_1") (pintype "passive"))
      (node (ref "EPD_C5") (pin "2") (pinfunction "2_2") (pintype "passive"))
      (node (ref "J1") (pin "15") (pinfunction "15_15") (pintype "bidirectional"))
      (node (ref "J1") (pin "16") (pinfunction "16_16") (pintype "bidirectional"))
      (node (ref "L5") (pin "1") (pinfunction "1_1") (pintype "passive"))
      (node (ref "Q1") (pin "3") (pinfunction "D_3") (pintype "bidirectional"))
    )
    (net (code "12") (name "EPD_BUSY") (class "Default")
      (node (ref "J1") (pin "9") (pinfunction "9_9") (pintype "bidirectional"))
      (node (ref "U1") (pin "P$AD12") (pinfunction "P0.17_P$AD12") (pintype "bidirectional"))
    )
    (net (code "13") (name "EPD_CS") (class "Default")
      (node (ref "J1") (pin "12") (pinfunction "12_12") (pintype "bidirectional"))
      (node (ref "U1") (pin "P$K2") (pinfunction "P0.05/AIN3_P$K2") (pintype "bidirectional"))
    )
    (net (code "14") (name "EPD_DC") (class "Default")
      (node (ref "J1") (pin "11") (pinfunction "11_11") (pintype "bidirectional"))
      (node (ref "U1") (pin "P$AD10") (pinfunction "P0.15_P$AD10") (pintype "bidirectional"))
    )
    (net (code "15") (name "EPD_RST") (class "Default")
      (node (ref "J1") (pin "10") (pinfunction "10_10") (pintype "bidirectional"))
      (node (ref "U1") (pin "P$AC11") (pinfunction "P0.16_P$AC11") (pintype "bidirectional"))
    )
    (net (code "16") (name "GDR") (class "Default")
      (node (ref "J1") (pin "2") (pinfunction "2_2") (pintype "bidirectional"))
      (node (ref "Q2") (pin "1") (pinfunction "G_1") (pintype "bidirectional"))
      (node (ref "R2_EP_DR") (pin "2") (pinfunction "2_2") (pintype "bidirectional"))
    )
    (net (code "17") (name "GND") (class "Default")
      (node (ref "C1") (pin "2") (pinfunction "2_2") (pintype "passive"))
      (node (ref "C1-EP-DR") (pin "2") (pinfunction "2_2") (pintype "passive"))
      (node (ref "C10") (pin "2") (pinfunction "2_2") (pintype "passive"))
      (node (ref "C11") (pin "2") (pinfunction "2_2") (pintype "passive"))
      (node (ref "C12") (pin "2") (pinfunction "2_2") (pintype "passive"))
      (node (ref "C13") (pin "2") (pinfunction "2_2") (pintype "passive"))
      (node (ref "C14") (pin "2") (pinfunction "2_2") (pintype "passive"))
      (node (ref "C15") (pin "2") (pinfunction "2_2") (pintype "passive"))
      (node (ref "C16") (pin "2") (pinfunction "2_2") (pintype "passive"))
      (node (ref "C17") (pin "1") (pinfunction "1_1") (pintype "passive"))
      (node (ref "C18") (pin "1") (pinfunction "1_1") (pintype "passive"))
      (node (ref "C19") (pin "2") (pinfunction "2_2") (pintype "passive"))
      (node (ref "C2") (pin "2") (pinfunction "2_2") (pintype "passive"))
      (node (ref "C20") (pin "2") (pinfunction "2_2") (pintype "passive"))
      (node (ref "C21") (pin "2") (pinfunction "2_2") (pintype "passive"))
      (node (ref "C22") (pin "2") (pinfunction "2_2") (pintype "passive"))
      (node (ref "C23") (pin "1") (pinfunction "1_1") (pintype "passive"))
      (node (ref "C24") (pin "1") (pinfunction "1_1") (pintype "passive"))
      (node (ref "C25") (pin "2") (pinfunction "2_2") (pintype "passive"))
      (node (ref "C27") (pin "2") (pinfunction "2_2") (pintype "passive"))
      (node (ref "C29") (pin "2") (pinfunction "2_2") (pintype "passive"))
      (node (ref "C3") (pin "2") (pinfunction "2_2") (pintype "passive"))
      (node (ref "C30") (pin "2") (pinfunction "2_2") (pintype "passive"))
      (node (ref "C31") (pin "2") (pinfunction "2_2") (pintype "passive"))
      (node (ref "C32") (pin "2") (pinfunction "2_2") (pintype "passive"))
      (node (ref "C33") (pin "2") (pinfunction "2_2") (pintype "passive"))
      (node (ref "C34") (pin "2") (pinfunction "2_2") (pintype "passive"))
      (node (ref "C37") (pin "2") (pinfunction "2_2") (pintype "passive"))
      (node (ref "C38") (pin "2") (pinfunction "2_2") (pintype "passive"))
      (node (ref "C39") (pin "2") (pinfunction "2_2") (pintype "passive"))
      (node (ref "C4") (pin "2") (pinfunction "2_2") (pintype "passive"))
      (node (ref "C42") (pin "2") (pinfunction "2_2") (pintype "passive"))
      (node (ref "C43") (pin "2") (pinfunction "2_2") (pintype "passive"))
      (node (ref "C5") (pin "2") (pinfunction "2_2") (pintype "passive"))
      (node (ref "C6") (pin "2") (pinfunction "2_2") (pintype "passive"))
      (node (ref "C7") (pin "2") (pinfunction "2_2") (pintype "passive"))
      (node (ref "C8") (pin "2") (pinfunction "2_2") (pintype "passive"))
      (node (ref "C9") (pin "2") (pinfunction "2_2") (pintype "passive"))
      (node (ref "D3") (pin "2") (pinfunction "GND_2") (pintype "bidirectional"))
      (node (ref "D4") (pin "1") (pinfunction "K_1") (pintype "bidirectional"))
      (node (ref "EPD_C1") (pin "1") (pinfunction "1_1") (pintype "passive"))
      (node (ref "EPD_C10") (pin "1") (pinfunction "1_1") (pintype "passive"))
      (node (ref "EPD_C11") (pin "1") (pinfunction "1_1") (pintype "passive"))
      (node (ref "EPD_C12") (pin "1") (pinfunction "1_1") (pintype "passive"))
      (node (ref "EPD_C2") (pin "1") (pinfunction "1_1") (pintype "passive"))
      (node (ref "EPD_C5") (pin "1") (pinfunction "1_1") (pintype "passive"))
      (node (ref "EPD_C6") (pin "1") (pinfunction "1_1") (pintype "passive"))
      (node (ref "EPD_C7") (pin "1") (pinfunction "1_1") (pintype "passive"))
      (node (ref "EPD_C8") (pin "1") (pinfunction "1_1") (pintype "passive"))
      (node (ref "EPD_C9") (pin "1") (pinfunction "1_1") (pintype "passive"))
      (node (ref "IC1") (pin "D2") (pinfunction "GND_D2") (pintype "bidirectional"))
      (node (ref "IC2") (pin "B1") (pinfunction "IN/TRIG_B1") (pintype "bidirectional"))
      (node (ref "IC2") (pin "B3") (pinfunction "GND_B3") (pintype "bidirectional"))
      (node (ref "IC3") (pin "8") (pinfunction "GNDIO_8") (pintype "bidirectional"))
      (node (ref "IC3") (pin "9") (pinfunction "GND_9") (pintype "bidirectional"))
      (node (ref "IC9") (pin "B1") (pinfunction "VSEL_B1") (pintype "bidirectional"))
      (node (ref "IC9") (pin "C1") (pinfunction "AGND_C1") (pintype "bidirectional"))
      (node (ref "IC9") (pin "C2") (pinfunction "PGND_1_C2") (pintype "bidirectional"))
      (node (ref "IC9") (pin "C3") (pinfunction "PGND_2_C3") (pintype "bidirectional"))
      (node (ref "J1") (pin "17") (pinfunction "17_17") (pintype "bidirectional"))
      (node (ref "J1") (pin "8") (pinfunction "8_8") (pintype "bidirectional"))
      (node (ref "J1") (pin "MP1") (pinfunction "MP1_MP1") (pintype "bidirectional"))
      (node (ref "J1") (pin "MP2") (pinfunction "MP2_MP2") (pintype "bidirectional"))
      (node (ref "J2") (pin "3") (pinfunction "3_3") (pintype "bidirectional"))
      (node (ref "J2") (pin "5") (pinfunction "5_5") (pintype "bidirectional"))
      (node (ref "J4") (pin "A12_B1") (pinfunction "GND_A12_B1") (pintype "power_in"))
      (node (ref "J4") (pin "A1_B12") (pinfunction "GND_A1_B12") (pintype "power_in"))
      (node (ref "J4") (pin "SH1") (pinfunction "SHIELD_SH1") (pintype "passive"))
      (node (ref "J4") (pin "SH2") (pinfunction "SHIELD_SH2") (pintype "passive"))
      (node (ref "J4") (pin "SH3") (pinfunction "SHIELD_SH3") (pintype "passive"))
      (node (ref "J4") (pin "SH4") (pinfunction "SHIELD_SH4") (pintype "passive"))
      (node (ref "R1_USB") (pin "1") (pinfunction "1_1") (pintype "bidirectional"))
      (node (ref "R2_EP_DR") (pin "1") (pinfunction "1_1") (pintype "bidirectional"))
      (node (ref "R2_USB") (pin "2") (pinfunction "2_2") (pintype "bidirectional"))
      (node (ref "R3") (pin "1") (pinfunction "1_1") (pintype "bidirectional"))
      (node (ref "R9") (pin "1") (pinfunction "1_1") (pintype "bidirectional"))
      (node (ref "R_TYPE_SEL") (pin "1") (pinfunction "1_1") (pintype "bidirectional"))
      (node (ref "SJ1") (pin "1") (pinfunction "1_1") (pintype "passive"))
      (node (ref "SW_DN") (pin "1") (pinfunction "1_1") (pintype "passive"))
      (node (ref "SW_ENT") (pin "1") (pinfunction "1_1") (pintype "passive"))
      (node (ref "SW_UP") (pin "1") (pinfunction "1_1") (pintype "passive"))
      (node (ref "TP_BAT_GND") (pin "TP") (pinfunction "TP_TP") (pintype "input"))
      (node (ref "TP_GND") (pin "TP") (pinfunction "TP_TP") (pintype "input"))
      (node (ref "U1") (pin "P$74") (pinfunction "VSS_PAD_P$74") (pintype "bidirectional"))
      (node (ref "U1") (pin "P$75") (pinfunction "VSS_PAD_P$75") (pintype "bidirectional"))
      (node (ref "U1") (pin "P$76") (pinfunction "VSS_PAD_P$76") (pintype "bidirectional"))
      (node (ref "U1") (pin "P$77") (pinfunction "VSS_PAD_P$77") (pintype "bidirectional"))
      (node (ref "U1") (pin "P$78") (pinfunction "VSS_PAD_P$78") (pintype "bidirectional"))
      (node (ref "U1") (pin "P$79") (pinfunction "VSS_PAD_P$79") (pintype "bidirectional"))
      (node (ref "U1") (pin "P$80") (pinfunction "VSS_PAD_P$80") (pintype "bidirectional"))
      (node (ref "U1") (pin "P$81") (pinfunction "VSS_PAD_P$81") (pintype "bidirectional"))
      (node (ref "U1") (pin "P$82") (pinfunction "VSS_PAD_P$82") (pintype "bidirectional"))
      (node (ref "U1") (pin "P$83") (pinfunction "VSS_PAD_P$83") (pintype "bidirectional"))
      (node (ref "U1") (pin "P$84") (pinfunction "VSS_PAD_P$84") (pintype "bidirectional"))
      (node (ref "U1") (pin "P$85") (pinfunction "VSS_PAD_P$85") (pintype "bidirectional"))
      (node (ref "U1") (pin "P$86") (pinfunction "VSS_PAD_P$86") (pintype "bidirectional"))
      (node (ref "U1") (pin "P$87") (pinfunction "VSS_PAD_P$87") (pintype "bidirectional"))
      (node (ref "U1") (pin "P$88") (pinfunction "VSS_PAD_P$88") (pintype "bidirectional"))
      (node (ref "U1") (pin "P$89") (pinfunction "VSS_PAD_P$89") (pintype "bidirectional"))
      (node (ref "U1") (pin "P$90") (pinfunction "VSS_PAD_P$90") (pintype "bidirectional"))
      (node (ref "U1") (pin "P$B7") (pinfunction "VSS_P$B7") (pintype "power_in"))
      (node (ref "U1") (pin "P$F23") (pinfunction "VSS_PA_P$F23") (pintype "bidirectional"))
      (node (ref "U3") (pin "1") (pinfunction "CTG_1") (pintype "power_in"))
      (node (ref "U3") (pin "4") (pinfunction "GND_4") (pintype "power_in"))
      (node (ref "U3") (pin "6") (pinfunction "QSTRT_6") (pintype "input"))
      (node (ref "U3") (pin "9") (pinfunction "EP_9") (pintype "power_in"))
      (node (ref "X1") (pin "2") (pinfunction "2_2") (pintype "passive"))
      (node (ref "X1") (pin "4") (pinfunction "4_4") (pintype "passive"))
    )
    (net (code "18") (name "HAPTIC_EN") (class "Default")
      (node (ref "IC2") (pin "A1") (pinfunction "EN_A1") (pintype "bidirectional"))
      (node (ref "U1") (pin "P$U1") (pinfunction "P0.12_P$U1") (pintype "bidirectional"))
    )
    (net (code "19") (name "IMU_INT1") (class "Default")
      (node (ref "IC3") (pin "5") (pinfunction "INT1_5") (pintype "bidirectional"))
      (node (ref "U1") (pin "P$N1") (pinfunction "P0.08_P$N1") (pintype "bidirectional"))
    )
    (net (code "20") (name "IMU_INT2") (class "Default")
      (node (ref "IC3") (pin "6") (pinfunction "INT2_6") (pintype "bidirectional"))
      (node (ref "U1") (pin "P$P2") (pinfunction "P1.08_P$P2") (pintype "bidirectional"))
    )
    (net (code "21") (name "LX1") (class "Default")
      (node (ref "IC9") (pin "B2") (pinfunction "SW1_1_B2") (pintype "bidirectional"))
      (node (ref "IC9") (pin "B3") (pinfunction "SW1_2_B3") (pintype "bidirectional"))
      (node (ref "L7") (pin "1") (pinfunction "1_1") (pintype "bidirectional"))
    )
    (net (code "22") (name "LX2") (class "Default")
      (node (ref "IC9") (pin "D2") (pinfunction "SW2_1_D2") (pintype "bidirectional"))
      (node (ref "IC9") (pin "D3") (pinfunction "SW2_2_D3") (pintype "bidirectional"))
      (node (ref "L7") (pin "2") (pinfunction "2_2") (pintype "bidirectional"))
    )
    (net (code "23") (name "MOSI") (class "Default")
      (node (ref "J1") (pin "14") (pinfunction "14_14") (pintype "bidirectional"))
      (node (ref "U1") (pin "P$B13") (pinfunction "P0.03/AIN1_P$B13") (pintype "bidirectional"))
    )
    (net (code "24") (name "Net-(D2-K)") (class "Default")
      (node (ref "C2-EP-DR") (pin "1") (pinfunction "1_1") (pintype "passive"))
      (node (ref "D2") (pin "1") (pinfunction "K_1") (pintype "bidirectional"))
      (node (ref "D4") (pin "2") (pinfunction "A_2") (pintype "bidirectional"))
    )
    (net (code "25") (name "Net-(D5-A)") (class "Default")
      (node (ref "C2-EP-DR") (pin "2") (pinfunction "2_2") (pintype "passive"))
      (node (ref "D5") (pin "2") (pinfunction "A_2") (pintype "bidirectional"))
      (node (ref "L5") (pin "2") (pinfunction "2_2") (pintype "passive"))
      (node (ref "Q2") (pin "3") (pinfunction "D_3") (pintype "bidirectional"))
    )
    (net (code "26") (name "Net-(EPD_C1-Pad2)") (class "Default")
      (node (ref "EPD_C1") (pin "2") (pinfunction "2_2") (pintype "passive"))
      (node (ref "J1") (pin "5") (pinfunction "5_5") (pintype "bidirectional"))
    )
    (net (code "27") (name "Net-(EPD_C2-Pad2)") (class "Default")
      (node (ref "EPD_C2") (pin "2") (pinfunction "2_2") (pintype "passive"))
      (node (ref "J1") (pin "4") (pinfunction "4_4") (pintype "bidirectional"))
    )
    (net (code "28") (name "Net-(EPD_C6-Pad2)") (class "Default")
      (node (ref "EPD_C6") (pin "2") (pinfunction "2_2") (pintype "passive"))
      (node (ref "J1") (pin "18") (pinfunction "18_18") (pintype "bidirectional"))
    )
    (net (code "29") (name "Net-(EPD_C7-Pad2)") (class "Default")
      (node (ref "EPD_C7") (pin "2") (pinfunction "2_2") (pintype "passive"))
      (node (ref "J1") (pin "19") (pinfunction "19_19") (pintype "bidirectional"))
    )
    (net (code "30") (name "Net-(EPD_C8-Pad2)") (class "Default")
      (node (ref "EPD_C8") (pin "2") (pinfunction "2_2") (pintype "passive"))
      (node (ref "J1") (pin "20") (pinfunction "20_20") (pintype "bidirectional"))
    )
    (net (code "31") (name "Net-(EPD_C10-Pad2)") (class "Default")
      (node (ref "EPD_C10") (pin "2") (pinfunction "2_2") (pintype "passive"))
      (node (ref "J1") (pin "22") (pinfunction "22_22") (pintype "bidirectional"))
    )
    (net (code "32") (name "Net-(EPD_C12-Pad2)") (class "Default")
      (node (ref "EPD_C12") (pin "2") (pinfunction "2_2") (pintype "passive"))
      (node (ref "J1") (pin "24") (pinfunction "24_24") (pintype "bidirectional"))
    )
    (net (code "33") (name "Net-(IC1-TS{slash}MR)") (class "Default")
      (node (ref "IC1") (pin "D1") (pinfunction "TS/MR_D1") (pintype "bidirectional"))
      (node (ref "R9") (pin "2") (pinfunction "2_2") (pintype "bidirectional"))
    )
    (net (code "34") (name "Net-(IC2-REG)") (class "Default")
      (node (ref "C32") (pin "1") (pinfunction "1_1") (pintype "passive"))
      (node (ref "IC2") (pin "A2") (pinfunction "REG_A2") (pintype "bidirectional"))
    )
    (net (code "35") (name "Net-(IC3-SDO)") (class "Default")
      (node (ref "IC3") (pin "1") (pinfunction "SDO_1") (pintype "bidirectional"))
      (node (ref "R3") (pin "2") (pinfunction "2_2") (pintype "bidirectional"))
    )
    (net (code "36") (name "Net-(IC9-SCL)") (class "Default")
      (node (ref "IC9") (pin "D1") (pinfunction "SCL_D1") (pintype "bidirectional"))
      (node (ref "R4") (pin "2") (pinfunction "2_2") (pintype "bidirectional"))
    )
    (net (code "37") (name "Net-(IC9-SDA)") (class "Default")
      (node (ref "IC9") (pin "E1") (pinfunction "SDA_E1") (pintype "bidirectional"))
      (node (ref "R2") (pin "2") (pinfunction "2_2") (pintype "bidirectional"))
    )
    (net (code "38") (name "Net-(J4-CC1)") (class "Default")
      (node (ref "J4") (pin "A5") (pinfunction "CC1_A5") (pintype "bidirectional"))
      (node (ref "R1_USB") (pin "2") (pinfunction "2_2") (pintype "bidirectional"))
    )
    (net (code "39") (name "Net-(J4-CC2)") (class "Default")
      (node (ref "J4") (pin "B5") (pinfunction "CC2_B5") (pintype "bidirectional"))
      (node (ref "R2_USB") (pin "1") (pinfunction "1_1") (pintype "bidirectional"))
    )
    (net (code "40") (name "Net-(L2-Pad2)") (class "Default")
      (node (ref "L2") (pin "2") (pinfunction "2_2") (pintype "passive"))
      (node (ref "L3") (pin "1") (pinfunction "1_1") (pintype "passive"))
    )
    (net (code "41") (name "Net-(R1_EP_DR-Pad1)") (class "Default")
      (node (ref "R1_EP_DR") (pin "1") (pinfunction "1_1") (pintype "bidirectional"))
      (node (ref "R_TYPE_SEL") (pin "2") (pinfunction "2_2") (pintype "bidirectional"))
      (node (ref "SJ1") (pin "2") (pinfunction "2_2") (pintype "passive"))
    )
    (net (code "42") (name "Net-(U1-ANT)") (class "Default")
      (node (ref "C3") (pin "1") (pinfunction "1_1") (pintype "passive"))
      (node (ref "L1") (pin "1") (pinfunction "1_1") (pintype "passive"))
      (node (ref "U1") (pin "P$H23") (pinfunction "ANT_P$H23") (pintype "bidirectional"))
    )
    (net (code "43") (name "Net-(U1-DCC)") (class "Default")
      (node (ref "L2") (pin "1") (pinfunction "1_1") (pintype "passive"))
      (node (ref "U1") (pin "P$B3") (pinfunction "DCC_P$B3") (pintype "output"))
    )
    (net (code "44") (name "Net-(U1-DEC2)") (class "Default")
      (node (ref "C13") (pin "1") (pinfunction "1_1") (pintype "passive"))
      (node (ref "U1") (pin "P$A18") (pinfunction "DEC2_P$A18") (pintype "bidirectional"))
    )
    (net (code "45") (name "Net-(U1-DEC3V3)") (class "Default")
      (node (ref "C20") (pin "1") (pinfunction "1_1") (pintype "passive"))
      (node (ref "U1") (pin "P$AC5") (pinfunction "DEC3V3_P$AC5") (pintype "bidirectional"))
    )
    (net (code "46") (name "Net-(U1-DEC5)") (class "Default")
      (node (ref "C9") (pin "1") (pinfunction "1_1") (pintype "passive"))
      (node (ref "U1") (pin "P$N24") (pinfunction "DEC5_P$N24") (pintype "bidirectional"))
    )
    (net (code "47") (name "Net-(U1-XC1)") (class "Default")
      (node (ref "C1") (pin "1") (pinfunction "1_1") (pintype "passive"))
      (node (ref "U1") (pin "P$B24") (pinfunction "XC1_P$B24") (pintype "input"))
      (node (ref "X1") (pin "1") (pinfunction "1_1") (pintype "passive"))
    )
    (net (code "48") (name "Net-(U1-XC2)") (class "Default")
      (node (ref "C2") (pin "1") (pinfunction "1_1") (pintype "passive"))
      (node (ref "U1") (pin "P$A23") (pinfunction "XC2_P$A23") (pintype "output"))
      (node (ref "X1") (pin "3") (pinfunction "3_3") (pintype "passive"))
    )
    (net (code "49") (name "OUT+") (class "Default")
      (node (ref "IC2") (pin "A3") (pinfunction "OUT+_A3") (pintype "bidirectional"))
      (node (ref "TP_OP") (pin "TP") (pinfunction "TP_TP") (pintype "input"))
    )
    (net (code "50") (name "OUT-") (class "Default")
      (node (ref "IC2") (pin "C3") (pinfunction "OUT-_C3") (pintype "bidirectional"))
      (node (ref "TP_ON") (pin "TP") (pinfunction "TP_TP") (pintype "input"))
    )
    (net (code "51") (name "P0.00{slash}XL1") (class "Default")
      (node (ref "C17") (pin "2") (pinfunction "2_2") (pintype "passive"))
      (node (ref "U1") (pin "P$D2") (pinfunction "P0.00/XL1_P$D2") (pintype "bidirectional"))
      (node (ref "X2") (pin "1") (pinfunction "1_1") (pintype "passive"))
    )
    (net (code "52") (name "P0.01{slash}XL2") (class "Default")
      (node (ref "C18") (pin "2") (pinfunction "2_2") (pintype "passive"))
      (node (ref "U1") (pin "P$F2") (pinfunction "P0.01/XL2_P$F2") (pintype "bidirectional"))
      (node (ref "X2") (pin "2") (pinfunction "2_2") (pintype "passive"))
    )
    (net (code "53") (name "P0.04") (class "Default")
      (node (ref "U1") (pin "P$J1") (pinfunction "P0.04/AIN2_P$J1") (pintype "bidirectional"))
    )
    (net (code "54") (name "P0.09") (class "Default")
      (node (ref "U1") (pin "P$L24") (pinfunction "P0.09/NFC1_P$L24") (pintype "bidirectional"))
    )
    (net (code "55") (name "P0.13") (class "Default")
      (node (ref "C30") (pin "1") (pinfunction "1_1") (pintype "passive"))
      (node (ref "R5") (pin "1") (pinfunction "1_1") (pintype "bidirectional"))
      (node (ref "SW_UP") (pin "2") (pinfunction "2_2") (pintype "passive"))
      (node (ref "U1") (pin "P$AD8") (pinfunction "P0.13_P$AD8") (pintype "bidirectional"))
    )
    (net (code "56") (name "P0.14") (class "Default")
      (node (ref "C31") (pin "1") (pinfunction "1_1") (pintype "passive"))
      (node (ref "R8") (pin "1") (pinfunction "1_1") (pintype "bidirectional"))
      (node (ref "SW_ENT") (pin "2") (pinfunction "2_2") (pintype "passive"))
      (node (ref "U1") (pin "P$AC9") (pinfunction "P0.14_P$AC9") (pintype "bidirectional"))
    )
    (net (code "57") (name "P0.19") (class "Default")
      (node (ref "U1") (pin "P$AC15") (pinfunction "P0.19_P$AC15") (pintype "bidirectional"))
    )
    (net (code "58") (name "P0.20") (class "Default")
      (node (ref "U1") (pin "P$AD16") (pinfunction "P0.20_P$AD16") (pintype "bidirectional"))
    )
    (net (code "59") (name "P0.21") (class "Default")
      (node (ref "U1") (pin "P$AC17") (pinfunction "P0.21_P$AC17") (pintype "bidirectional"))
    )
    (net (code "60") (name "P0.22") (class "Default")
      (node (ref "U1") (pin "P$AD18") (pinfunction "P0.22_P$AD18") (pintype "bidirectional"))
    )
    (net (code "61") (name "P0.23") (class "Default")
      (node (ref "U1") (pin "P$AC19") (pinfunction "P0.23_P$AC19") (pintype "bidirectional"))
    )
    (net (code "62") (name "P0.24") (class "Default")
      (node (ref "U1") (pin "P$AD20") (pinfunction "P0.24_P$AD20") (pintype "bidirectional"))
    )
    (net (code "63") (name "P0.25") (class "Default")
      (node (ref "U1") (pin "P$AC21") (pinfunction "P0.25_P$AC21") (pintype "bidirectional"))
    )
    (net (code "64") (name "P0.26") (class "Default")
      (node (ref "U1") (pin "P$G1") (pinfunction "P0.26_P$G1") (pintype "bidirectional"))
    )
    (net (code "65") (name "P0.27") (class "Default")
      (node (ref "U1") (pin "P$H2") (pinfunction "P0.27_P$H2") (pintype "bidirectional"))
    )
    (net (code "66") (name "P0.28") (class "Default")
      (node (ref "U1") (pin "P$B11") (pinfunction "P0.28/AIN4_P$B11") (pintype "bidirectional"))
    )
    (net (code "67") (name "P0.29") (class "Default")
      (node (ref "U1") (pin "P$A10") (pinfunction "P0.29/AIN5_P$A10") (pintype "bidirectional"))
    )
    (net (code "68") (name "P0.30") (class "Default")
      (node (ref "U1") (pin "P$B9") (pinfunction "P0.30/AIN6_P$B9") (pintype "bidirectional"))
    )
    (net (code "69") (name "P0.31") (class "Default")
      (node (ref "U1") (pin "P$A8") (pinfunction "P0.31/AIN7_P$A8") (pintype "bidirectional"))
    )
    (net (code "70") (name "P1.01") (class "Default")
      (node (ref "Q1") (pin "1") (pinfunction "G_1") (pintype "bidirectional"))
      (node (ref "R_PWR_EPD") (pin "1") (pinfunction "1_1") (pintype "bidirectional"))
      (node (ref "U1") (pin "P$Y23") (pinfunction "P1.01_P$Y23") (pintype "bidirectional"))
    )
    (net (code "71") (name "P1.02") (class "Default")
      (node (ref "C29") (pin "1") (pinfunction "1_1") (pintype "passive"))
      (node (ref "R7") (pin "1") (pinfunction "1_1") (pintype "bidirectional"))
      (node (ref "SW_DN") (pin "2") (pinfunction "2_2") (pintype "passive"))
      (node (ref "U1") (pin "P$W24") (pinfunction "P1.02_P$W24") (pintype "bidirectional"))
    )
    (net (code "72") (name "P1.03") (class "Default")
      (node (ref "U1") (pin "P$V23") (pinfunction "P1.03_P$V23") (pintype "bidirectional"))
    )
    (net (code "73") (name "P1.04") (class "Default")
      (node (ref "U1") (pin "P$U24") (pinfunction "P1.04_P$U24") (pintype "bidirectional"))
    )
    (net (code "74") (name "P1.05") (class "Default")
      (node (ref "U1") (pin "P$T23") (pinfunction "P1.05_P$T23") (pintype "bidirectional"))
    )
    (net (code "75") (name "P1.06") (class "Default")
      (node (ref "U1") (pin "P$R24") (pinfunction "P1.06_P$R24") (pintype "bidirectional"))
    )
    (net (code "76") (name "P1.07") (class "Default")
      (node (ref "U1") (pin "P$P23") (pinfunction "P1.07_P$P23") (pintype "bidirectional"))
    )
    (net (code "77") (name "P1.09") (class "Default")
      (node (ref "U1") (pin "P$R1") (pinfunction "P1.09_P$R1") (pintype "bidirectional"))
    )
    (net (code "78") (name "P1.10") (class "Default")
      (node (ref "U1") (pin "P$A20") (pinfunction "P1.10_P$A20") (pintype "bidirectional"))
    )
    (net (code "79") (name "P1.11") (class "Default")
      (node (ref "U1") (pin "P$B19") (pinfunction "P1.11_P$B19") (pintype "bidirectional"))
    )
    (net (code "80") (name "P1.12") (class "Default")
      (node (ref "U1") (pin "P$B17") (pinfunction "P1.12_P$B17") (pintype "bidirectional"))
    )
    (net (code "81") (name "P1.13") (class "Default")
      (node (ref "U1") (pin "P$A16") (pinfunction "P1.13_P$A16") (pintype "bidirectional"))
    )
    (net (code "82") (name "P1.14") (class "Default")
      (node (ref "U1") (pin "P$B15") (pinfunction "P1.14_P$B15") (pintype "bidirectional"))
    )
    (net (code "83") (name "P1.15") (class "Default")
      (node (ref "U1") (pin "P$A14") (pinfunction "P1.15_P$A14") (pintype "bidirectional"))
    )
    (net (code "84") (name "PMIC_INT") (class "Default")
      (node (ref "IC1") (pin "A1") (pinfunction "~{INT}_A1") (pintype "bidirectional"))
      (node (ref "U1") (pin "P$T2") (pinfunction "P0.11_P$T2") (pintype "bidirectional"))
    )
    (net (code "85") (name "PREVGH") (class "Default")
      (node (ref "D5") (pin "1") (pinfunction "K_1") (pintype "bidirectional"))
      (node (ref "EPD_C9") (pin "2") (pinfunction "2_2") (pintype "passive"))
      (node (ref "J1") (pin "21") (pinfunction "21_21") (pintype "bidirectional"))
    )
    (net (code "86") (name "PREVGL") (class "Default")
      (node (ref "D2") (pin "2") (pinfunction "A_2") (pintype "bidirectional"))
      (node (ref "EPD_C11") (pin "2") (pinfunction "2_2") (pintype "passive"))
      (node (ref "J1") (pin "23") (pinfunction "23_23") (pintype "bidirectional"))
    )
    (net (code "87") (name "RESE") (class "Default")
      (node (ref "J1") (pin "3") (pinfunction "3_3") (pintype "bidirectional"))
      (node (ref "Q2") (pin "2") (pinfunction "S_2") (pintype "bidirectional"))
      (node (ref "R1_EP_DR") (pin "2") (pinfunction "2_2") (pintype "bidirectional"))
    )
    (net (code "88") (name "RESET") (class "Default")
      (node (ref "J2") (pin "6") (pinfunction "6_6") (pintype "bidirectional"))
      (node (ref "TP_RESET") (pin "TP") (pinfunction "TP_TP") (pintype "input"))
      (node (ref "U1") (pin "P$AC13") (pinfunction "P0.18/RESET_P$AC13") (pintype "bidirectional"))
    )
    (net (code "89") (name "RF") (class "Default")
      (node (ref "ANT1") (pin "1") (pinfunction "FEED_1") (pintype "input"))
      (node (ref "C22") (pin "1") (pinfunction "1_1") (pintype "passive"))
      (node (ref "C4") (pin "1") (pinfunction "1_1") (pintype "passive"))
      (node (ref "L1") (pin "2") (pinfunction "2_2") (pintype "passive"))
    )
    (net (code "90") (name "SCK") (class "Default")
      (node (ref "J1") (pin "13") (pinfunction "13_13") (pintype "bidirectional"))
      (node (ref "U1") (pin "P$A12") (pinfunction "P0.02/AIN0_P$A12") (pintype "bidirectional"))
    )
    (net (code "91") (name "SCL{slash}1.4C") (class "Default")
      (node (ref "IC2") (pin "C1") (pinfunction "SCL_C1") (pintype "bidirectional"))
      (node (ref "U3") (pin "7") (pinfunction "SCL_7") (pintype "input"))
    )
    (net (code "92") (name "SCL{slash}2.4C") (class "Default")
      (node (ref "IC1") (pin "B1") (pinfunction "SCL_B1") (pintype "bidirectional"))
      (node (ref "IC3") (pin "12") (pinfunction "SCX_12") (pintype "bidirectional"))
      (node (ref "R17") (pin "2") (pinfunction "2_2") (pintype "bidirectional"))
      (node (ref "R4") (pin "1") (pinfunction "1_1") (pintype "bidirectional"))
      (node (ref "TP_SCL") (pin "TP") (pinfunction "TP_TP") (pintype "input"))
      (node (ref "U1") (pin "P$M2") (pinfunction "P0.07_P$M2") (pintype "bidirectional"))
    )
    (net (code "93") (name "SDA{slash}1.4C") (class "Default")
      (node (ref "IC2") (pin "B2") (pinfunction "SDA_B2") (pintype "bidirectional"))
      (node (ref "U3") (pin "8") (pinfunction "SDA_8") (pintype "bidirectional"))
    )
    (net (code "94") (name "SDA{slash}2.4C") (class "Default")
      (node (ref "IC1") (pin "C1") (pinfunction "SDA_C1") (pintype "bidirectional"))
      (node (ref "IC3") (pin "2") (pinfunction "SDX_2") (pintype "bidirectional"))
      (node (ref "R18") (pin "2") (pinfunction "2_2") (pintype "bidirectional"))
      (node (ref "R2") (pin "1") (pinfunction "1_1") (pintype "bidirectional"))
      (node (ref "TP_SDA") (pin "TP") (pinfunction "TP_TP") (pintype "input"))
      (node (ref "U1") (pin "P$L1") (pinfunction "P0.06_P$L1") (pintype "bidirectional"))
    )
    (net (code "95") (name "SWDCLK") (class "Default")
      (node (ref "J2") (pin "4") (pinfunction "4_4") (pintype "bidirectional"))
      (node (ref "TP_SWDCLK") (pin "TP") (pinfunction "TP_TP") (pintype "input"))
      (node (ref "U1") (pin "P$AA24") (pinfunction "SWDCLK_P$AA24") (pintype "input"))
    )
    (net (code "96") (name "SWDIO") (class "Default")
      (node (ref "J2") (pin "2") (pinfunction "2_2") (pintype "bidirectional"))
      (node (ref "TP_SWDIO") (pin "TP") (pinfunction "TP_TP") (pintype "input"))
      (node (ref "U1") (pin "P$AC24") (pinfunction "SWDIO_P$AC24") (pintype "bidirectional"))
    )
    (net (code "97") (name "SWO") (class "Default")
      (node (ref "TP_SWO") (pin "TP") (pinfunction "TP_TP") (pintype "input"))
      (node (ref "U1") (pin "P$AD22") (pinfunction "P1.00_P$AD22") (pintype "bidirectional"))
    )
    (net (code "98") (name "VBAT{slash}1.2A") (class "Default")
      (node (ref "C27") (pin "1") (pinfunction "1_1") (pintype "passive"))
      (node (ref "TP_VBAT") (pin "TP") (pinfunction "TP_TP") (pintype "input"))
      (node (ref "U3") (pin "2") (pinfunction "CELL_2") (pintype "power_in"))
      (node (ref "U3") (pin "3") (pinfunction "VDD_3") (pintype "power_in"))
    )
    (net (code "99") (name "VBAT{slash}2.5C") (class "Default")
      (node (ref "C37") (pin "1") (pinfunction "1_1") (pintype "passive"))
      (node (ref "IC1") (pin "C2") (pinfunction "BAT_C2") (pintype "bidirectional"))
    )
    (net (code "100") (name "VBUS{slash}1.5D") (class "Default")
      (node (ref "C42") (pin "1") (pinfunction "1_1") (pintype "passive"))
      (node (ref "C43") (pin "1") (pinfunction "1_1") (pintype "passive"))
      (node (ref "D3") (pin "5") (pinfunction "VBUS_5") (pintype "bidirectional"))
      (node (ref "J4") (pin "A4_B9") (pinfunction "VBUS_A4_B9") (pintype "power_in"))
      (node (ref "J4") (pin "A9_B4") (pinfunction "VBUS_A9_B4") (pintype "power_in"))
    )
    (net (code "101") (name "VBUS{slash}2.6D") (class "Default")
      (node (ref "C21") (pin "1") (pinfunction "1_1") (pintype "passive"))
      (node (ref "C38") (pin "1") (pinfunction "1_1") (pintype "passive"))
      (node (ref "IC1") (pin "A2") (pinfunction "IN_A2") (pintype "bidirectional"))
      (node (ref "U1") (pin "P$AD2") (pinfunction "VBUS_P$AD2") (pintype "power_in"))
    )
    (net (code "102") (name "VREG") (class "Default")
      (node (ref "C23") (pin "2") (pinfunction "2_2") (pintype "passive"))
      (node (ref "C24") (pin "2") (pinfunction "2_2") (pintype "passive"))
      (node (ref "C39") (pin "1") (pinfunction "1_1") (pintype "passive"))
      (node (ref "IC1") (pin "B2") (pinfunction "SYS_B2") (pintype "bidirectional"))
      (node (ref "IC9") (pin "A1") (pinfunction "EN_A1") (pintype "bidirectional"))
      (node (ref "IC9") (pin "A2") (pinfunction "VIN_1_A2") (pintype "bidirectional"))
      (node (ref "IC9") (pin "A3") (pinfunction "VIN_2_A3") (pintype "bidirectional"))
      (node (ref "TP_VREG") (pin "TP") (pinfunction "TP_TP") (pintype "input"))
    )
    (net (code "103") (name "unconnected-(ANT1-NC-Pad2)") (class "Default")
      (node (ref "ANT1") (pin "2") (pinfunction "NC_2") (pintype "no_connect"))
    )
    (net (code "104") (name "unconnected-(IC3-ASCL-Pad11)") (class "Default")
      (node (ref "IC3") (pin "11") (pinfunction "ASCL_11") (pintype "bidirectional"))
    )
    (net (code "105") (name "unconnected-(IC3-ASDA-Pad4)") (class "Default")
      (node (ref "IC3") (pin "4") (pinfunction "ASDA_4") (pintype "bidirectional"))
    )
    (net (code "106") (name "unconnected-(J1-Pad1)") (class "Default")
      (node (ref "J1") (pin "1") (pinfunction "1_1") (pintype "bidirectional"))
    )
    (net (code "107") (name "unconnected-(J1-Pad6)") (class "Default")
      (node (ref "J1") (pin "6") (pinfunction "6_6") (pintype "bidirectional"))
    )
    (net (code "108") (name "unconnected-(J1-Pad7)") (class "Default")
      (node (ref "J1") (pin "7") (pinfunction "7_7") (pintype "bidirectional"))
    )
    (net (code "109") (name "unconnected-(J4-SBU1-PadA8)") (class "Default")
      (node (ref "J4") (pin "A8") (pinfunction "SBU1_A8") (pintype "bidirectional"))
    )
    (net (code "110") (name "unconnected-(J4-SBU2-PadB8)") (class "Default")
      (node (ref "J4") (pin "B8") (pinfunction "SBU2_B8") (pintype "bidirectional"))
    )
    (net (code "111") (name "unconnected-(U1-DCCH-PadP$AB2)") (class "Default")
      (node (ref "U1") (pin "P$AB2") (pinfunction "DCCH_P$AB2") (pintype "bidirectional"))
    )
  )
)
